# NET_232_USART_SD_FLASH.net
KiCad netlist of a schematic drawn in Altium Designer
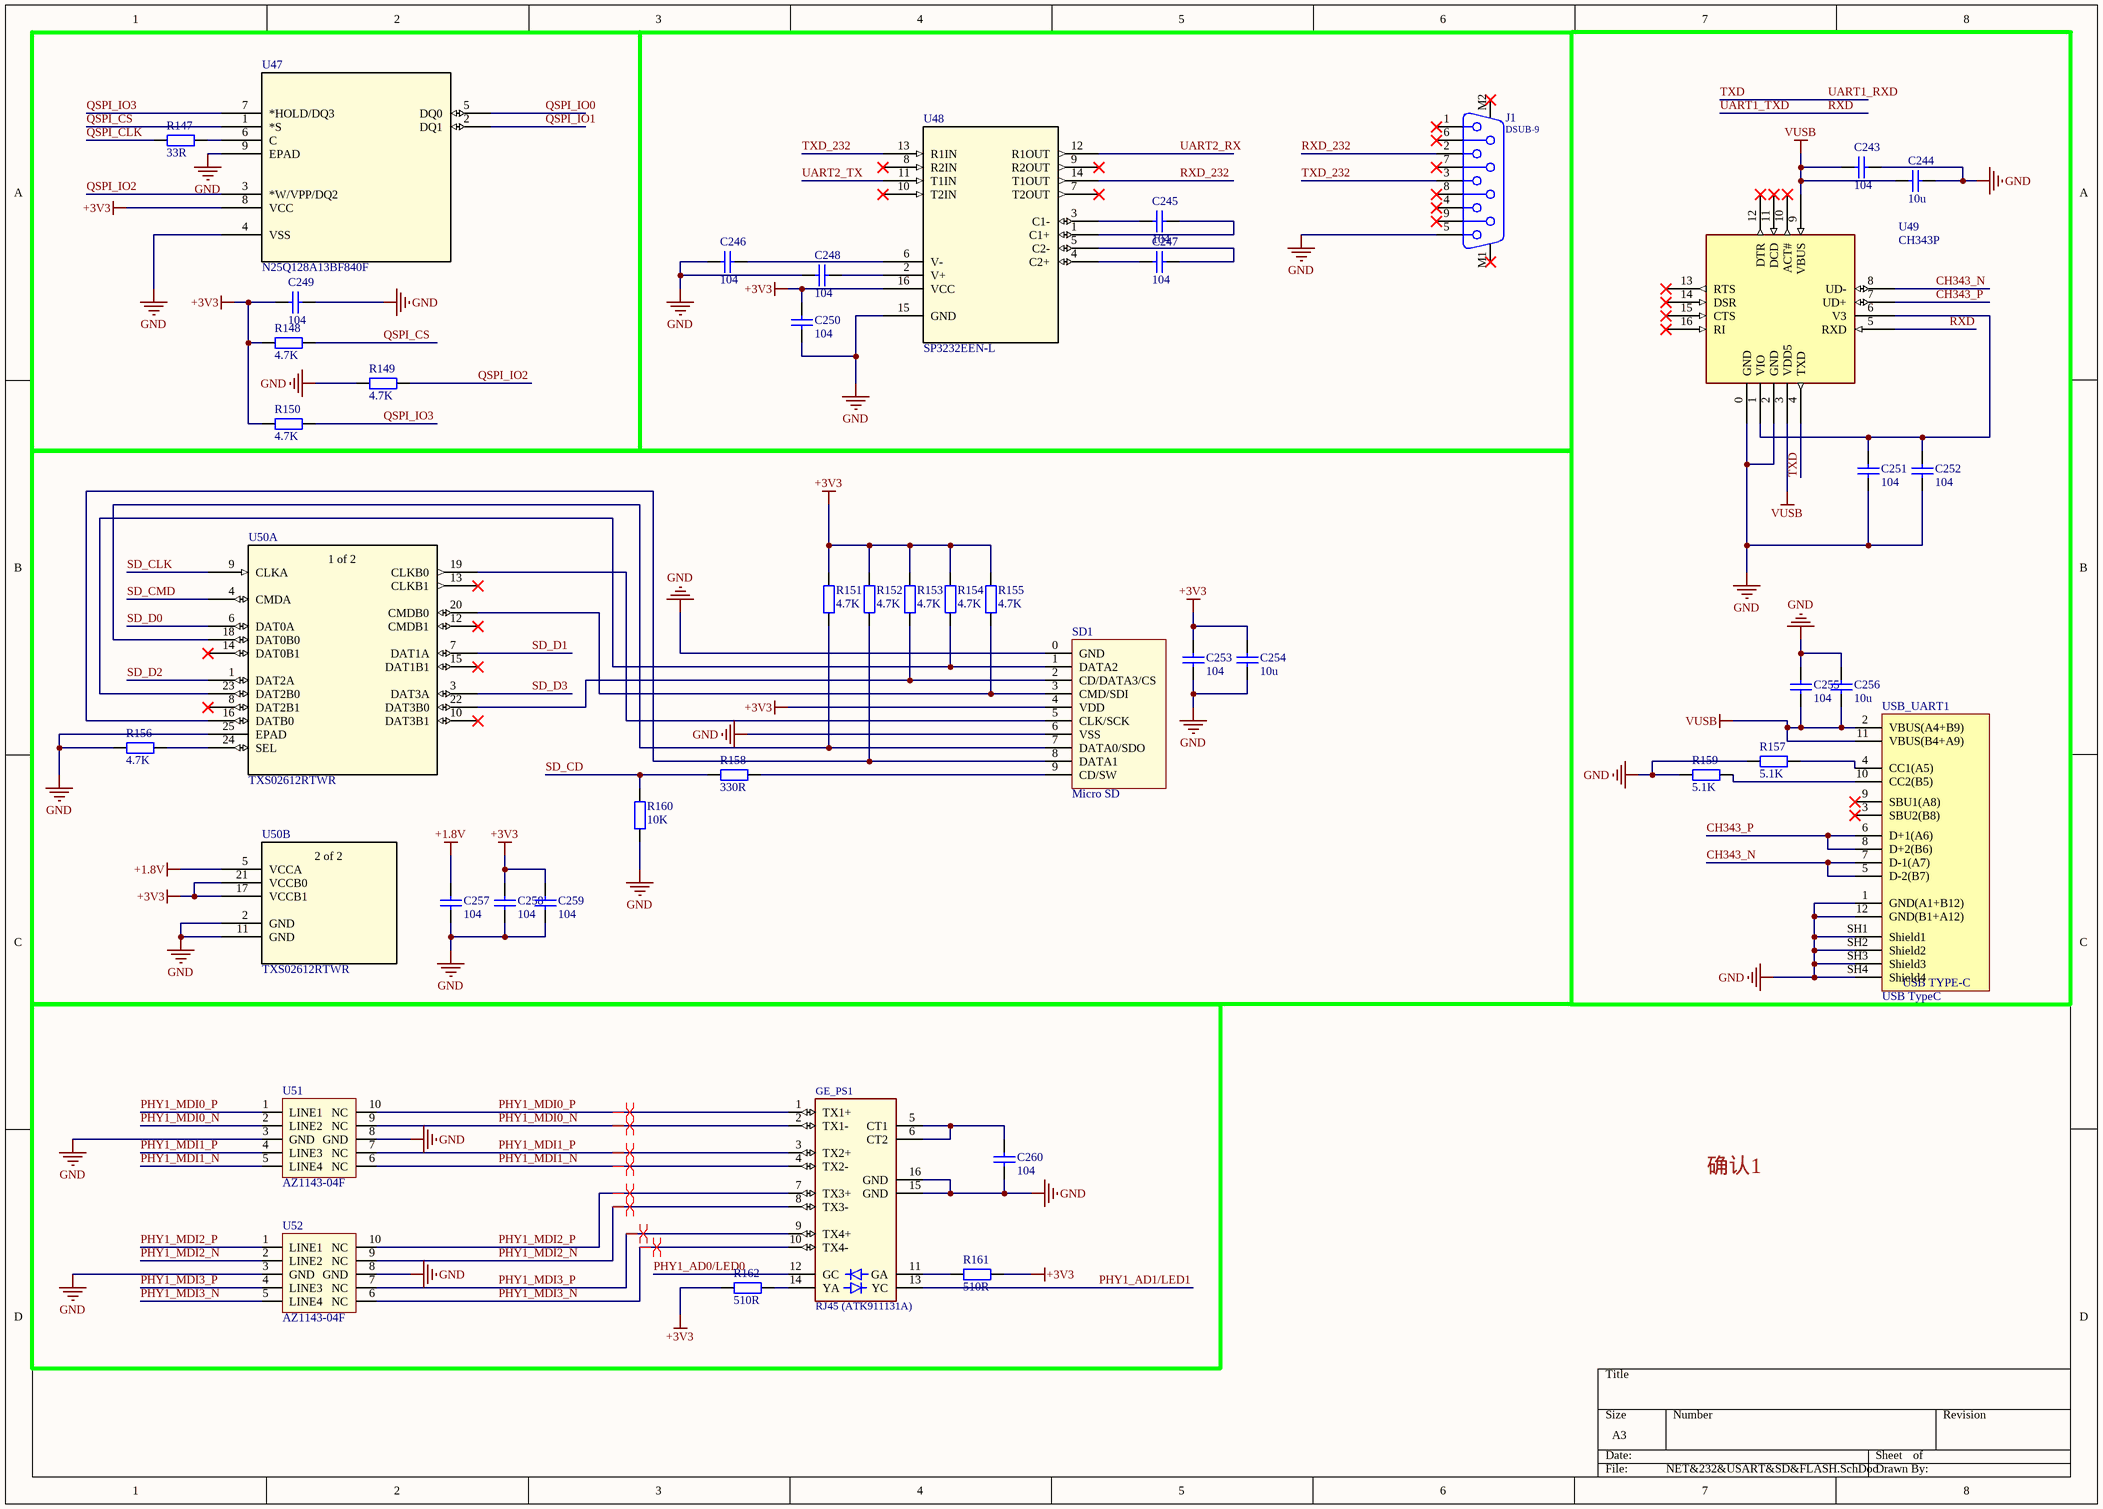
[diagram p0: NET&232&USART&SD&FLASH.SchDoc]

(export (version "E")
  (design (tool "Eeschema 10.0.6"))
  (components
    (comp (ref "C243")
      (value "104")
      (footprint "C0402_L")
      (description "贴片电容/MLCC电容")
      (libsource (lib "0.1 - 电阻-电容-电感-保险丝-晶振-晶体-磁珠-电位器-法拉电容-馈通电容") (part "C"))
    )
    (comp (ref "C244")
      (value "10u")
      (footprint "C0402_L")
      (description "贴片电容/MLCC电容")
      (libsource (lib "0.1 - 电阻-电容-电感-保险丝-晶振-晶体-磁珠-电位器-法拉电容-馈通电容") (part "C"))
    )
    (comp (ref "C245")
      (value "104")
      (footprint "C0402_L")
      (description "贴片电容/MLCC电容")
      (libsource (lib "0.1 - 电阻-电容-电感-保险丝-晶振-晶体-磁珠-电位器-法拉电容-馈通电容") (part "C"))
    )
    (comp (ref "C246")
      (value "104")
      (footprint "C0402_L")
      (description "贴片电容/MLCC电容")
      (libsource (lib "0.1 - 电阻-电容-电感-保险丝-晶振-晶体-磁珠-电位器-法拉电容-馈通电容") (part "C"))
    )
    (comp (ref "C247")
      (value "104")
      (footprint "C0402_L")
      (description "贴片电容/MLCC电容")
      (libsource (lib "0.1 - 电阻-电容-电感-保险丝-晶振-晶体-磁珠-电位器-法拉电容-馈通电容") (part "C"))
    )
    (comp (ref "C248")
      (value "104")
      (footprint "C0402_L")
      (description "贴片电容/MLCC电容")
      (libsource (lib "0.1 - 电阻-电容-电感-保险丝-晶振-晶体-磁珠-电位器-法拉电容-馈通电容") (part "C"))
    )
    (comp (ref "C249")
      (value "104")
      (footprint "C0402_L")
      (description "贴片电容/MLCC电容")
      (libsource (lib "0.1 - 电阻-电容-电感-保险丝-晶振-晶体-磁珠-电位器-法拉电容-馈通电容") (part "C"))
    )
    (comp (ref "C250")
      (value "104")
      (footprint "C0402_L")
      (description "贴片电容/MLCC电容")
      (libsource (lib "0.1 - 电阻-电容-电感-保险丝-晶振-晶体-磁珠-电位器-法拉电容-馈通电容") (part "C"))
    )
    (comp (ref "C251")
      (value "104")
      (footprint "C0402_L")
      (description "贴片电容/MLCC电容")
      (libsource (lib "0.1 - 电阻-电容-电感-保险丝-晶振-晶体-磁珠-电位器-法拉电容-馈通电容") (part "C"))
    )
    (comp (ref "C252")
      (value "104")
      (footprint "C0402_L")
      (description "贴片电容/MLCC电容")
      (libsource (lib "0.1 - 电阻-电容-电感-保险丝-晶振-晶体-磁珠-电位器-法拉电容-馈通电容") (part "C"))
    )
    (comp (ref "C253")
      (value "104")
      (footprint "C0402_L")
      (description "贴片电容/MLCC电容")
      (libsource (lib "0.1 - 电阻-电容-电感-保险丝-晶振-晶体-磁珠-电位器-法拉电容-馈通电容") (part "C"))
    )
    (comp (ref "C254")
      (value "10u")
      (footprint "C0402_L")
      (description "贴片电容/MLCC电容")
      (libsource (lib "0.1 - 电阻-电容-电感-保险丝-晶振-晶体-磁珠-电位器-法拉电容-馈通电容") (part "C"))
    )
    (comp (ref "C255")
      (value "104")
      (footprint "C0402_L")
      (description "贴片电容/MLCC电容")
      (libsource (lib "0.1 - 电阻-电容-电感-保险丝-晶振-晶体-磁珠-电位器-法拉电容-馈通电容") (part "C"))
    )
    (comp (ref "C256")
      (value "10u")
      (footprint "C0402_L")
      (description "贴片电容/MLCC电容")
      (libsource (lib "0.1 - 电阻-电容-电感-保险丝-晶振-晶体-磁珠-电位器-法拉电容-馈通电容") (part "C"))
    )
    (comp (ref "C257")
      (value "104")
      (footprint "C0402_L")
      (description "贴片电容/MLCC电容")
      (libsource (lib "0.1 - 电阻-电容-电感-保险丝-晶振-晶体-磁珠-电位器-法拉电容-馈通电容") (part "C"))
    )
    (comp (ref "C258")
      (value "104")
      (footprint "C0402_L")
      (description "贴片电容/MLCC电容")
      (libsource (lib "0.1 - 电阻-电容-电感-保险丝-晶振-晶体-磁珠-电位器-法拉电容-馈通电容") (part "C"))
    )
    (comp (ref "C259")
      (value "104")
      (footprint "C0402_L")
      (description "贴片电容/MLCC电容")
      (libsource (lib "0.1 - 电阻-电容-电感-保险丝-晶振-晶体-磁珠-电位器-法拉电容-馈通电容") (part "C"))
    )
    (comp (ref "C260")
      (value "104")
      (footprint "C0402_L")
      (description "贴片电容/MLCC电容")
      (libsource (lib "0.1 - 电阻-电容-电感-保险丝-晶振-晶体-磁珠-电位器-法拉电容-馈通电容") (part "C"))
    )
    (comp (ref "GE_PS1")
      (value "RJ45 (ATK911131A)")
      (footprint "HR911131A")
      (description "千兆以太网接口")
      (libsource (lib "领航者ZYNQ底板SCH&PCB封装库") (part "HR911131A/C_1"))
    )
    (comp (ref "J1")
      (value "DSUB-9")
      (footprint "DB-9-H")
      (description "DSUB-9Pin母座")
      (libsource (lib "0.6 - 电源_音频_USB Type-C_HDMI_XT60_5557_D-SUB_RJ45_SD-TF_SIM插座") (part "DSUB-9"))
    )
    (comp (ref "R147")
      (value "33R")
      (footprint "R0402_L")
      (description "贴片电阻")
      (libsource (lib "0.1 - 电阻-电容-电感-保险丝-晶振-晶体-磁珠-电位器-法拉电容-馈通电容") (part "R"))
    )
    (comp (ref "R148")
      (value "4.7K")
      (footprint "R0402_L")
      (description "贴片电阻")
      (libsource (lib "0.1 - 电阻-电容-电感-保险丝-晶振-晶体-磁珠-电位器-法拉电容-馈通电容") (part "R"))
    )
    (comp (ref "R149")
      (value "4.7K")
      (footprint "R0402_L")
      (description "贴片电阻")
      (libsource (lib "0.1 - 电阻-电容-电感-保险丝-晶振-晶体-磁珠-电位器-法拉电容-馈通电容") (part "R"))
    )
    (comp (ref "R150")
      (value "4.7K")
      (footprint "R0402_L")
      (description "贴片电阻")
      (libsource (lib "0.1 - 电阻-电容-电感-保险丝-晶振-晶体-磁珠-电位器-法拉电容-馈通电容") (part "R"))
    )
    (comp (ref "R151")
      (value "4.7K")
      (footprint "R0402_L")
      (description "贴片电阻")
      (libsource (lib "0.1 - 电阻-电容-电感-保险丝-晶振-晶体-磁珠-电位器-法拉电容-馈通电容") (part "R"))
    )
    (comp (ref "R152")
      (value "4.7K")
      (footprint "R0402_L")
      (description "贴片电阻")
      (libsource (lib "0.1 - 电阻-电容-电感-保险丝-晶振-晶体-磁珠-电位器-法拉电容-馈通电容") (part "R"))
    )
    (comp (ref "R153")
      (value "4.7K")
      (footprint "R0402_L")
      (description "贴片电阻")
      (libsource (lib "0.1 - 电阻-电容-电感-保险丝-晶振-晶体-磁珠-电位器-法拉电容-馈通电容") (part "R"))
    )
    (comp (ref "R154")
      (value "4.7K")
      (footprint "R0402_L")
      (description "贴片电阻")
      (libsource (lib "0.1 - 电阻-电容-电感-保险丝-晶振-晶体-磁珠-电位器-法拉电容-馈通电容") (part "R"))
    )
    (comp (ref "R155")
      (value "4.7K")
      (footprint "R0402_L")
      (description "贴片电阻")
      (libsource (lib "0.1 - 电阻-电容-电感-保险丝-晶振-晶体-磁珠-电位器-法拉电容-馈通电容") (part "R"))
    )
    (comp (ref "R156")
      (value "4.7K")
      (footprint "R0402_L")
      (description "贴片电阻")
      (libsource (lib "0.1 - 电阻-电容-电感-保险丝-晶振-晶体-磁珠-电位器-法拉电容-馈通电容") (part "R"))
    )
    (comp (ref "R157")
      (value "5.1K")
      (footprint "R0402_L")
      (description "贴片电阻")
      (libsource (lib "0.1 - 电阻-电容-电感-保险丝-晶振-晶体-磁珠-电位器-法拉电容-馈通电容") (part "R"))
    )
    (comp (ref "R158")
      (value "330R")
      (footprint "R0402_L")
      (description "贴片电阻")
      (libsource (lib "0.1 - 电阻-电容-电感-保险丝-晶振-晶体-磁珠-电位器-法拉电容-馈通电容") (part "R"))
    )
    (comp (ref "R159")
      (value "5.1K")
      (footprint "R0402_L")
      (description "贴片电阻")
      (libsource (lib "0.1 - 电阻-电容-电感-保险丝-晶振-晶体-磁珠-电位器-法拉电容-馈通电容") (part "R"))
    )
    (comp (ref "R160")
      (value "10K")
      (footprint "R0402_L")
      (description "贴片电阻")
      (libsource (lib "0.1 - 电阻-电容-电感-保险丝-晶振-晶体-磁珠-电位器-法拉电容-馈通电容") (part "R"))
    )
    (comp (ref "R161")
      (value "510R")
      (footprint "R0402_L")
      (description "贴片电阻")
      (libsource (lib "0.1 - 电阻-电容-电感-保险丝-晶振-晶体-磁珠-电位器-法拉电容-馈通电容") (part "R"))
    )
    (comp (ref "R162")
      (value "510R")
      (footprint "R0402_L")
      (description "贴片电阻")
      (libsource (lib "0.1 - 电阻-电容-电感-保险丝-晶振-晶体-磁珠-电位器-法拉电容-馈通电容") (part "R"))
    )
    (comp (ref "SD1")
      (value "Micro SD")
      (footprint "Micro SD")
      (description "Micro SD卡")
      (fields (field (name "版权归属") "源创客"))
      (libsource (lib "领航者ZYNQ底板SCH&PCB封装库") (part "Micro SD"))
    )
    (comp (ref "U47")
      (value "N25Q128A13BF840F")
      (footprint "VDFPN8_8X6_MRN")
      (description "No Description Available")
      (libsource (lib "N25Q128A13BF840F") (part "N25Q128A13BF840F"))
    )
    (comp (ref "U48")
      (value "SP3232EEN-L")
      (footprint "NSOIC-16_MXL")
      (description "No Description Available")
      (libsource (lib "SP3232EEN-L") (part "SP3232EEN-L"))
    )
    (comp (ref "U49")
      (value "CH343P")
      (footprint "QFN16_3X3")
      (description "USB to high speed enhanced TTL Serial / UART")
      (libsource (lib "CHXXX") (part "CH343P"))
    )
    (comp (ref "U50")
      (value "TXS02612RTWR")
      (footprint "RTW24_2P45X2P45")
      (description "No Description Available")
      (libsource (lib "TXS02612RTWR") (part "TXS02612RTWR"))
    )
    (comp (ref "U51")
      (value "AZ1143-04F")
      (footprint "DFN2510P10E")
      (description "ESD保护二极管阵列")
      (libsource (lib "领航者ZYNQ底板SCH&PCB封装库") (part "AZ1143-04F"))
    )
    (comp (ref "U52")
      (value "AZ1143-04F")
      (footprint "DFN2510P10E")
      (description "ESD保护二极管阵列")
      (libsource (lib "领航者ZYNQ底板SCH&PCB封装库") (part "AZ1143-04F"))
    )
    (comp (ref "USB_UART1")
      (value "USB TypeC")
      (footprint "USB Type-C")
      (description "12P TypeC 母座")
      (libsource (lib "领航者ZYNQ底板SCH&PCB封装库") (part "USB Type-C"))
    )
  )
  (nets
    (net (code "1") (name "+1.8V") (class "Default")
      (node (ref "C257") (pin "1") (pinfunction "1_1") (pintype "passive"))
      (node (ref "U50") (pin "5") (pinfunction "VCCA_5") (pintype "power_in"))
    )
    (net (code "2") (name "+3V3") (class "Default")
      (node (ref "C249") (pin "2") (pinfunction "2_2") (pintype "passive"))
      (node (ref "C250") (pin "1") (pinfunction "1_1") (pintype "passive"))
      (node (ref "C253") (pin "1") (pinfunction "1_1") (pintype "passive"))
      (node (ref "C254") (pin "1") (pinfunction "1_1") (pintype "passive"))
      (node (ref "C258") (pin "1") (pinfunction "1_1") (pintype "passive"))
      (node (ref "C259") (pin "1") (pinfunction "1_1") (pintype "passive"))
      (node (ref "R148") (pin "2") (pinfunction "2_2") (pintype "passive"))
      (node (ref "R150") (pin "2") (pinfunction "2_2") (pintype "passive"))
      (node (ref "R151") (pin "1") (pinfunction "1_1") (pintype "passive"))
      (node (ref "R152") (pin "1") (pinfunction "1_1") (pintype "passive"))
      (node (ref "R153") (pin "1") (pinfunction "1_1") (pintype "passive"))
      (node (ref "R154") (pin "1") (pinfunction "1_1") (pintype "passive"))
      (node (ref "R155") (pin "1") (pinfunction "1_1") (pintype "passive"))
      (node (ref "R161") (pin "2") (pinfunction "2_2") (pintype "passive"))
      (node (ref "R162") (pin "1") (pinfunction "1_1") (pintype "passive"))
      (node (ref "SD1") (pin "4") (pinfunction "VDD_4") (pintype "passive"))
      (node (ref "U47") (pin "8") (pinfunction "VCC_8") (pintype "power_in"))
      (node (ref "U48") (pin "16") (pinfunction "VCC_16") (pintype "power_in"))
      (node (ref "U50") (pin "17") (pinfunction "VCCB1_17") (pintype "power_in"))
      (node (ref "U50") (pin "21") (pinfunction "VCCB0_21") (pintype "power_in"))
    )
    (net (code "3") (name "/CH343_N") (class "Default")
      (node (ref "U49") (pin "8") (pinfunction "UD-_8") (pintype "bidirectional"))
      (node (ref "USB_UART1") (pin "5") (pinfunction "D-2(B7)_5") (pintype "passive"))
      (node (ref "USB_UART1") (pin "7") (pinfunction "D-1(A7)_7") (pintype "passive"))
    )
    (net (code "4") (name "/CH343_P") (class "Default")
      (node (ref "U49") (pin "7") (pinfunction "UD+_7") (pintype "bidirectional"))
      (node (ref "USB_UART1") (pin "6") (pinfunction "D+1(A6)_6") (pintype "passive"))
      (node (ref "USB_UART1") (pin "8") (pinfunction "D+2(B6)_8") (pintype "passive"))
    )
    (net (code "5") (name "/PHY1_AD0{slash}LED0") (class "Default")
      (node (ref "GE_PS1") (pin "12") (pinfunction "GC_12") (pintype "passive"))
    )
    (net (code "6") (name "/PHY1_AD1{slash}LED1") (class "Default")
      (node (ref "GE_PS1") (pin "13") (pinfunction "YC_13") (pintype "passive"))
    )
    (net (code "7") (name "/PHY1_MDI0_N") (class "Default")
      (node (ref "GE_PS1") (pin "2") (pinfunction "TX1-_2") (pintype "bidirectional"))
      (node (ref "U51") (pin "2") (pinfunction "LINE2_2") (pintype "passive"))
      (node (ref "U51") (pin "9") (pinfunction "NC_9") (pintype "passive"))
    )
    (net (code "8") (name "/PHY1_MDI0_P") (class "Default")
      (node (ref "GE_PS1") (pin "1") (pinfunction "TX1+_1") (pintype "bidirectional"))
      (node (ref "U51") (pin "1") (pinfunction "LINE1_1") (pintype "passive"))
      (node (ref "U51") (pin "10") (pinfunction "NC_10") (pintype "passive"))
    )
    (net (code "9") (name "/PHY1_MDI1_N") (class "Default")
      (node (ref "GE_PS1") (pin "4") (pinfunction "TX2-_4") (pintype "bidirectional"))
      (node (ref "U51") (pin "5") (pinfunction "LINE4_5") (pintype "passive"))
      (node (ref "U51") (pin "6") (pinfunction "NC_6") (pintype "passive"))
    )
    (net (code "10") (name "/PHY1_MDI1_P") (class "Default")
      (node (ref "GE_PS1") (pin "3") (pinfunction "TX2+_3") (pintype "bidirectional"))
      (node (ref "U51") (pin "4") (pinfunction "LINE3_4") (pintype "passive"))
      (node (ref "U51") (pin "7") (pinfunction "NC_7") (pintype "passive"))
    )
    (net (code "11") (name "/PHY1_MDI2_N") (class "Default")
      (node (ref "GE_PS1") (pin "8") (pinfunction "TX3-_8") (pintype "bidirectional"))
      (node (ref "U52") (pin "2") (pinfunction "LINE2_2") (pintype "passive"))
      (node (ref "U52") (pin "9") (pinfunction "NC_9") (pintype "passive"))
    )
    (net (code "12") (name "/PHY1_MDI2_P") (class "Default")
      (node (ref "GE_PS1") (pin "7") (pinfunction "TX3+_7") (pintype "bidirectional"))
      (node (ref "U52") (pin "1") (pinfunction "LINE1_1") (pintype "passive"))
      (node (ref "U52") (pin "10") (pinfunction "NC_10") (pintype "passive"))
    )
    (net (code "13") (name "/PHY1_MDI3_N") (class "Default")
      (node (ref "GE_PS1") (pin "10") (pinfunction "TX4-_10") (pintype "bidirectional"))
      (node (ref "U52") (pin "5") (pinfunction "LINE4_5") (pintype "passive"))
      (node (ref "U52") (pin "6") (pinfunction "NC_6") (pintype "passive"))
    )
    (net (code "14") (name "/PHY1_MDI3_P") (class "Default")
      (node (ref "GE_PS1") (pin "9") (pinfunction "TX4+_9") (pintype "bidirectional"))
      (node (ref "U52") (pin "4") (pinfunction "LINE3_4") (pintype "passive"))
      (node (ref "U52") (pin "7") (pinfunction "NC_7") (pintype "passive"))
    )
    (net (code "15") (name "/QSPI_CLK") (class "Default")
      (node (ref "R147") (pin "2") (pinfunction "2_2") (pintype "passive"))
    )
    (net (code "16") (name "/QSPI_CS") (class "Default")
      (node (ref "R148") (pin "1") (pinfunction "1_1") (pintype "passive"))
      (node (ref "U47") (pin "1") (pinfunction "*S_1") (pintype "passive"))
    )
    (net (code "17") (name "/QSPI_IO0") (class "Default")
      (node (ref "U47") (pin "5") (pinfunction "DQ0_5") (pintype "bidirectional"))
    )
    (net (code "18") (name "/QSPI_IO1") (class "Default")
      (node (ref "U47") (pin "2") (pinfunction "DQ1_2") (pintype "bidirectional"))
    )
    (net (code "19") (name "/QSPI_IO2") (class "Default")
      (node (ref "R149") (pin "1") (pinfunction "1_1") (pintype "passive"))
      (node (ref "U47") (pin "3") (pinfunction "*W/VPP/DQ2_3") (pintype "power_in"))
    )
    (net (code "20") (name "/QSPI_IO3") (class "Default")
      (node (ref "R150") (pin "1") (pinfunction "1_1") (pintype "passive"))
      (node (ref "U47") (pin "7") (pinfunction "*HOLD/DQ3_7") (pintype "passive"))
    )
    (net (code "21") (name "/RXD") (class "Default")
      (node (ref "U49") (pin "5") (pinfunction "RXD_5") (pintype "input"))
    )
    (net (code "22") (name "/RXD_232") (class "Default")
      (node (ref "J1") (pin "2") (pinfunction "2_2") (pintype "passive"))
      (node (ref "U48") (pin "14") (pinfunction "T1OUT_14") (pintype "output"))
    )
    (net (code "23") (name "/SD_CD") (class "Default")
      (node (ref "R158") (pin "2") (pinfunction "2_2") (pintype "passive"))
      (node (ref "R160") (pin "1") (pinfunction "1_1") (pintype "passive"))
    )
    (net (code "24") (name "/SD_CLK") (class "Default")
      (node (ref "U50") (pin "9") (pinfunction "CLKA_9") (pintype "input"))
    )
    (net (code "25") (name "/SD_CMD") (class "Default")
      (node (ref "U50") (pin "4") (pinfunction "CMDA_4") (pintype "bidirectional"))
    )
    (net (code "26") (name "/SD_D0") (class "Default")
      (node (ref "U50") (pin "6") (pinfunction "DAT0A_6") (pintype "bidirectional"))
    )
    (net (code "27") (name "/SD_D1") (class "Default")
      (node (ref "U50") (pin "7") (pinfunction "DAT1A_7") (pintype "bidirectional"))
    )
    (net (code "28") (name "/SD_D2") (class "Default")
      (node (ref "U50") (pin "1") (pinfunction "DAT2A_1") (pintype "bidirectional"))
    )
    (net (code "29") (name "/SD_D3") (class "Default")
      (node (ref "U50") (pin "3") (pinfunction "DAT3A_3") (pintype "bidirectional"))
    )
    (net (code "30") (name "/TXD") (class "Default")
      (node (ref "U49") (pin "4") (pinfunction "TXD_4") (pintype "output"))
    )
    (net (code "31") (name "/TXD_232") (class "Default")
      (node (ref "J1") (pin "3") (pinfunction "3_3") (pintype "passive"))
      (node (ref "U48") (pin "13") (pinfunction "R1IN_13") (pintype "input"))
    )
    (net (code "32") (name "/UART2_RX") (class "Default")
      (node (ref "U48") (pin "12") (pinfunction "R1OUT_12") (pintype "output"))
    )
    (net (code "33") (name "/UART2_TX") (class "Default")
      (node (ref "U48") (pin "11") (pinfunction "T1IN_11") (pintype "input"))
    )
    (net (code "34") (name "GND") (class "Default")
      (node (ref "C243") (pin "2") (pinfunction "2_2") (pintype "passive"))
      (node (ref "C244") (pin "2") (pinfunction "2_2") (pintype "passive"))
      (node (ref "C246") (pin "2") (pinfunction "2_2") (pintype "passive"))
      (node (ref "C248") (pin "2") (pinfunction "2_2") (pintype "passive"))
      (node (ref "C249") (pin "1") (pinfunction "1_1") (pintype "passive"))
      (node (ref "C250") (pin "2") (pinfunction "2_2") (pintype "passive"))
      (node (ref "C251") (pin "1") (pinfunction "1_1") (pintype "passive"))
      (node (ref "C252") (pin "1") (pinfunction "1_1") (pintype "passive"))
      (node (ref "C253") (pin "2") (pinfunction "2_2") (pintype "passive"))
      (node (ref "C254") (pin "2") (pinfunction "2_2") (pintype "passive"))
      (node (ref "C255") (pin "2") (pinfunction "2_2") (pintype "passive"))
      (node (ref "C256") (pin "2") (pinfunction "2_2") (pintype "passive"))
      (node (ref "C257") (pin "2") (pinfunction "2_2") (pintype "passive"))
      (node (ref "C258") (pin "2") (pinfunction "2_2") (pintype "passive"))
      (node (ref "C259") (pin "2") (pinfunction "2_2") (pintype "passive"))
      (node (ref "C260") (pin "2") (pinfunction "2_2") (pintype "passive"))
      (node (ref "GE_PS1") (pin "15") (pinfunction "GND_15") (pintype "power_in"))
      (node (ref "GE_PS1") (pin "16") (pinfunction "GND_16") (pintype "power_in"))
      (node (ref "J1") (pin "5") (pinfunction "5_5") (pintype "passive"))
      (node (ref "R149") (pin "2") (pinfunction "2_2") (pintype "passive"))
      (node (ref "R156") (pin "2") (pinfunction "2_2") (pintype "passive"))
      (node (ref "R157") (pin "1") (pinfunction "1_1") (pintype "passive"))
      (node (ref "R159") (pin "1") (pinfunction "1_1") (pintype "passive"))
      (node (ref "R160") (pin "2") (pinfunction "2_2") (pintype "passive"))
      (node (ref "SD1") (pin "0") (pinfunction "GND_0") (pintype "passive"))
      (node (ref "SD1") (pin "6") (pinfunction "VSS_6") (pintype "passive"))
      (node (ref "U47") (pin "4") (pinfunction "VSS_4") (pintype "power_in"))
      (node (ref "U47") (pin "9") (pinfunction "EPAD_9") (pintype "passive"))
      (node (ref "U48") (pin "15") (pinfunction "GND_15") (pintype "power_in"))
      (node (ref "U49") (pin "0") (pinfunction "GND_0") (pintype "power_in"))
      (node (ref "U49") (pin "2") (pinfunction "GND_2") (pintype "power_in"))
      (node (ref "U50") (pin "11") (pinfunction "GND_11") (pintype "power_in"))
      (node (ref "U50") (pin "2") (pinfunction "GND_2") (pintype "power_in"))
      (node (ref "U50") (pin "25") (pinfunction "EPAD_25") (pintype "passive"))
      (node (ref "U51") (pin "3") (pinfunction "GND_3") (pintype "passive"))
      (node (ref "U51") (pin "8") (pinfunction "GND_8") (pintype "passive"))
      (node (ref "U52") (pin "3") (pinfunction "GND_3") (pintype "passive"))
      (node (ref "U52") (pin "8") (pinfunction "GND_8") (pintype "passive"))
      (node (ref "USB_UART1") (pin "1") (pinfunction "GND(A1+B12)_1") (pintype "passive"))
      (node (ref "USB_UART1") (pin "12") (pinfunction "GND(B1+A12)_12") (pintype "passive"))
      (node (ref "USB_UART1") (pin "SH1") (pinfunction "Shield1_SH1") (pintype "passive"))
      (node (ref "USB_UART1") (pin "SH2") (pinfunction "Shield2_SH2") (pintype "passive"))
      (node (ref "USB_UART1") (pin "SH3") (pinfunction "Shield3_SH3") (pintype "passive"))
      (node (ref "USB_UART1") (pin "SH4") (pinfunction "Shield4_SH4") (pintype "passive"))
    )
    (net (code "35") (name "Net-(GE_PS1-CT1)") (class "Default")
      (node (ref "C260") (pin "1") (pinfunction "1_1") (pintype "passive"))
      (node (ref "GE_PS1") (pin "5") (pinfunction "CT1_5") (pintype "passive"))
      (node (ref "GE_PS1") (pin "6") (pinfunction "CT2_6") (pintype "passive"))
    )
    (net (code "36") (name "Net-(GE_PS1-GA)") (class "Default")
      (node (ref "GE_PS1") (pin "11") (pinfunction "GA_11") (pintype "passive"))
      (node (ref "R161") (pin "1") (pinfunction "1_1") (pintype "passive"))
    )
    (net (code "37") (name "Net-(GE_PS1-YA)") (class "Default")
      (node (ref "GE_PS1") (pin "14") (pinfunction "YA_14") (pintype "passive"))
      (node (ref "R162") (pin "2") (pinfunction "2_2") (pintype "passive"))
    )
    (net (code "38") (name "Net-(SD1-CD{slash}DATA3{slash}CS)") (class "Default")
      (node (ref "R153") (pin "2") (pinfunction "2_2") (pintype "passive"))
      (node (ref "SD1") (pin "2") (pinfunction "CD/DATA3/CS_2") (pintype "passive"))
      (node (ref "U50") (pin "22") (pinfunction "DAT3B0_22") (pintype "bidirectional"))
    )
    (net (code "39") (name "Net-(SD1-CD{slash}SW)") (class "Default")
      (node (ref "R158") (pin "1") (pinfunction "1_1") (pintype "passive"))
      (node (ref "SD1") (pin "9") (pinfunction "CD/SW_9") (pintype "passive"))
    )
    (net (code "40") (name "Net-(SD1-CLK{slash}SCK)") (class "Default")
      (node (ref "SD1") (pin "5") (pinfunction "CLK/SCK_5") (pintype "passive"))
      (node (ref "U50") (pin "19") (pinfunction "CLKB0_19") (pintype "output"))
    )
    (net (code "41") (name "Net-(SD1-CMD{slash}SDI)") (class "Default")
      (node (ref "R155") (pin "2") (pinfunction "2_2") (pintype "passive"))
      (node (ref "SD1") (pin "3") (pinfunction "CMD/SDI_3") (pintype "passive"))
      (node (ref "U50") (pin "20") (pinfunction "CMDB0_20") (pintype "bidirectional"))
    )
    (net (code "42") (name "Net-(SD1-DATA0{slash}SDO)") (class "Default")
      (node (ref "R151") (pin "2") (pinfunction "2_2") (pintype "passive"))
      (node (ref "SD1") (pin "7") (pinfunction "DATA0/SDO_7") (pintype "passive"))
      (node (ref "U50") (pin "18") (pinfunction "DAT0B0_18") (pintype "bidirectional"))
    )
    (net (code "43") (name "Net-(SD1-DATA1)") (class "Default")
      (node (ref "R152") (pin "2") (pinfunction "2_2") (pintype "passive"))
      (node (ref "SD1") (pin "8") (pinfunction "DATA1_8") (pintype "passive"))
      (node (ref "U50") (pin "16") (pinfunction "DATB0_16") (pintype "bidirectional"))
    )
    (net (code "44") (name "Net-(SD1-DATA2)") (class "Default")
      (node (ref "R154") (pin "2") (pinfunction "2_2") (pintype "passive"))
      (node (ref "SD1") (pin "1") (pinfunction "DATA2_1") (pintype "passive"))
      (node (ref "U50") (pin "23") (pinfunction "DAT2B0_23") (pintype "bidirectional"))
    )
    (net (code "45") (name "Net-(U47-C)") (class "Default")
      (node (ref "R147") (pin "1") (pinfunction "1_1") (pintype "passive"))
      (node (ref "U47") (pin "6") (pinfunction "C_6") (pintype "passive"))
    )
    (net (code "46") (name "Net-(U48-C1+)") (class "Default")
      (node (ref "C245") (pin "1") (pinfunction "1_1") (pintype "passive"))
      (node (ref "U48") (pin "1") (pinfunction "C1+_1") (pintype "bidirectional"))
    )
    (net (code "47") (name "Net-(U48-C1-)") (class "Default")
      (node (ref "C245") (pin "2") (pinfunction "2_2") (pintype "passive"))
      (node (ref "U48") (pin "3") (pinfunction "C1-_3") (pintype "bidirectional"))
    )
    (net (code "48") (name "Net-(U48-C2+)") (class "Default")
      (node (ref "C247") (pin "2") (pinfunction "2_2") (pintype "passive"))
      (node (ref "U48") (pin "4") (pinfunction "C2+_4") (pintype "bidirectional"))
    )
    (net (code "49") (name "Net-(U48-C2-)") (class "Default")
      (node (ref "C247") (pin "1") (pinfunction "1_1") (pintype "passive"))
      (node (ref "U48") (pin "5") (pinfunction "C2-_5") (pintype "bidirectional"))
    )
    (net (code "50") (name "Net-(U48-V+)") (class "Default")
      (node (ref "C248") (pin "1") (pinfunction "1_1") (pintype "passive"))
      (node (ref "U48") (pin "2") (pinfunction "V+_2") (pintype "power_in"))
    )
    (net (code "51") (name "Net-(U48-V-)") (class "Default")
      (node (ref "C246") (pin "1") (pinfunction "1_1") (pintype "passive"))
      (node (ref "U48") (pin "6") (pinfunction "V-_6") (pintype "power_in"))
    )
    (net (code "52") (name "Net-(U49-V3)") (class "Default")
      (node (ref "C251") (pin "2") (pinfunction "2_2") (pintype "passive"))
      (node (ref "C252") (pin "2") (pinfunction "2_2") (pintype "passive"))
      (node (ref "U49") (pin "1") (pinfunction "VIO_1") (pintype "power_in"))
      (node (ref "U49") (pin "6") (pinfunction "V3_6") (pintype "power_in"))
    )
    (net (code "53") (name "Net-(U50A-SEL)") (class "Default")
      (node (ref "R156") (pin "1") (pinfunction "1_1") (pintype "passive"))
      (node (ref "U50") (pin "24") (pinfunction "SEL_24") (pintype "bidirectional"))
    )
    (net (code "54") (name "Net-(USB_UART1-CC1(A5))") (class "Default")
      (node (ref "R157") (pin "2") (pinfunction "2_2") (pintype "passive"))
      (node (ref "USB_UART1") (pin "4") (pinfunction "CC1(A5)_4") (pintype "passive"))
    )
    (net (code "55") (name "Net-(USB_UART1-CC2(B5))") (class "Default")
      (node (ref "R159") (pin "2") (pinfunction "2_2") (pintype "passive"))
      (node (ref "USB_UART1") (pin "10") (pinfunction "CC2(B5)_10") (pintype "passive"))
    )
    (net (code "56") (name "VUSB") (class "Default")
      (node (ref "C243") (pin "1") (pinfunction "1_1") (pintype "passive"))
      (node (ref "C244") (pin "1") (pinfunction "1_1") (pintype "passive"))
      (node (ref "C255") (pin "1") (pinfunction "1_1") (pintype "passive"))
      (node (ref "C256") (pin "1") (pinfunction "1_1") (pintype "passive"))
      (node (ref "U49") (pin "3") (pinfunction "VDD5_3") (pintype "power_in"))
      (node (ref "U49") (pin "9") (pinfunction "VBUS_9") (pintype "input"))
      (node (ref "USB_UART1") (pin "11") (pinfunction "VBUS(B4+A9)_11") (pintype "passive"))
      (node (ref "USB_UART1") (pin "2") (pinfunction "VBUS(A4+B9)_2") (pintype "passive"))
    )
    (net (code "57") (name "unconnected-(J1-Pad1)") (class "Default")
      (node (ref "J1") (pin "1") (pinfunction "1_1") (pintype "passive+no_connect"))
    )
    (net (code "58") (name "unconnected-(J1-Pad4)") (class "Default")
      (node (ref "J1") (pin "4") (pinfunction "4_4") (pintype "passive+no_connect"))
    )
    (net (code "59") (name "unconnected-(J1-Pad6)") (class "Default")
      (node (ref "J1") (pin "6") (pinfunction "6_6") (pintype "passive+no_connect"))
    )
    (net (code "60") (name "unconnected-(J1-Pad7)") (class "Default")
      (node (ref "J1") (pin "7") (pinfunction "7_7") (pintype "passive+no_connect"))
    )
    (net (code "61") (name "unconnected-(J1-Pad8)") (class "Default")
      (node (ref "J1") (pin "8") (pinfunction "8_8") (pintype "passive+no_connect"))
    )
    (net (code "62") (name "unconnected-(J1-Pad9)") (class "Default")
      (node (ref "J1") (pin "9") (pinfunction "9_9") (pintype "passive+no_connect"))
    )
    (net (code "63") (name "unconnected-(J1-PadM1)") (class "Default")
      (node (ref "J1") (pin "M1") (pinfunction "M1_M1") (pintype "passive+no_connect"))
    )
    (net (code "64") (name "unconnected-(J1-PadM2)") (class "Default")
      (node (ref "J1") (pin "M2") (pinfunction "M2_M2") (pintype "passive+no_connect"))
    )
    (net (code "65") (name "unconnected-(U48-R2IN-Pad8)") (class "Default")
      (node (ref "U48") (pin "8") (pinfunction "R2IN_8") (pintype "input+no_connect"))
    )
    (net (code "66") (name "unconnected-(U48-R2OUT-Pad9)") (class "Default")
      (node (ref "U48") (pin "9") (pinfunction "R2OUT_9") (pintype "output+no_connect"))
    )
    (net (code "67") (name "unconnected-(U48-T2IN-Pad10)") (class "Default")
      (node (ref "U48") (pin "10") (pinfunction "T2IN_10") (pintype "input+no_connect"))
    )
    (net (code "68") (name "unconnected-(U48-T2OUT-Pad7)") (class "Default")
      (node (ref "U48") (pin "7") (pinfunction "T2OUT_7") (pintype "output+no_connect"))
    )
    (net (code "69") (name "unconnected-(U49-ACT#-Pad10)") (class "Default")
      (node (ref "U49") (pin "10") (pinfunction "ACT#_10") (pintype "output+no_connect"))
    )
    (net (code "70") (name "unconnected-(U49-CTS-Pad15)") (class "Default")
      (node (ref "U49") (pin "15") (pinfunction "CTS_15") (pintype "input+no_connect"))
    )
    (net (code "71") (name "unconnected-(U49-DCD-Pad11)") (class "Default")
      (node (ref "U49") (pin "11") (pinfunction "DCD_11") (pintype "input+no_connect"))
    )
    (net (code "72") (name "unconnected-(U49-DSR-Pad14)") (class "Default")
      (node (ref "U49") (pin "14") (pinfunction "DSR_14") (pintype "input+no_connect"))
    )
    (net (code "73") (name "unconnected-(U49-DTR-Pad12)") (class "Default")
      (node (ref "U49") (pin "12") (pinfunction "DTR_12") (pintype "output+no_connect"))
    )
    (net (code "74") (name "unconnected-(U49-RI-Pad16)") (class "Default")
      (node (ref "U49") (pin "16") (pinfunction "RI_16") (pintype "input+no_connect"))
    )
    (net (code "75") (name "unconnected-(U49-RTS-Pad13)") (class "Default")
      (node (ref "U49") (pin "13") (pinfunction "RTS_13") (pintype "output+no_connect"))
    )
    (net (code "76") (name "unconnected-(U50A-CLKB1-Pad13)") (class "Default")
      (node (ref "U50") (pin "13") (pinfunction "CLKB1_13") (pintype "output+no_connect"))
    )
    (net (code "77") (name "unconnected-(U50A-CMDB1-Pad12)") (class "Default")
      (node (ref "U50") (pin "12") (pinfunction "CMDB1_12") (pintype "bidirectional+no_connect"))
    )
    (net (code "78") (name "unconnected-(U50A-DAT0B1-Pad14)") (class "Default")
      (node (ref "U50") (pin "14") (pinfunction "DAT0B1_14") (pintype "bidirectional+no_connect"))
    )
    (net (code "79") (name "unconnected-(U50A-DAT1B1-Pad15)") (class "Default")
      (node (ref "U50") (pin "15") (pinfunction "DAT1B1_15") (pintype "bidirectional+no_connect"))
    )
    (net (code "80") (name "unconnected-(U50A-DAT2B1-Pad8)") (class "Default")
      (node (ref "U50") (pin "8") (pinfunction "DAT2B1_8") (pintype "bidirectional+no_connect"))
    )
    (net (code "81") (name "unconnected-(U50A-DAT3B1-Pad10)") (class "Default")
      (node (ref "U50") (pin "10") (pinfunction "DAT3B1_10") (pintype "bidirectional+no_connect"))
    )
    (net (code "82") (name "unconnected-(USB_UART1-SBU1(A8)-Pad9)") (class "Default")
      (node (ref "USB_UART1") (pin "9") (pinfunction "SBU1(A8)_9") (pintype "passive+no_connect"))
    )
    (net (code "83") (name "unconnected-(USB_UART1-SBU2(B8)-Pad3)") (class "Default")
      (node (ref "USB_UART1") (pin "3") (pinfunction "SBU2(B8)_3") (pintype "passive+no_connect"))
    )
  )
)
